# PCB_CAPA1.net
KiCad netlist of a schematic drawn in EAGLE
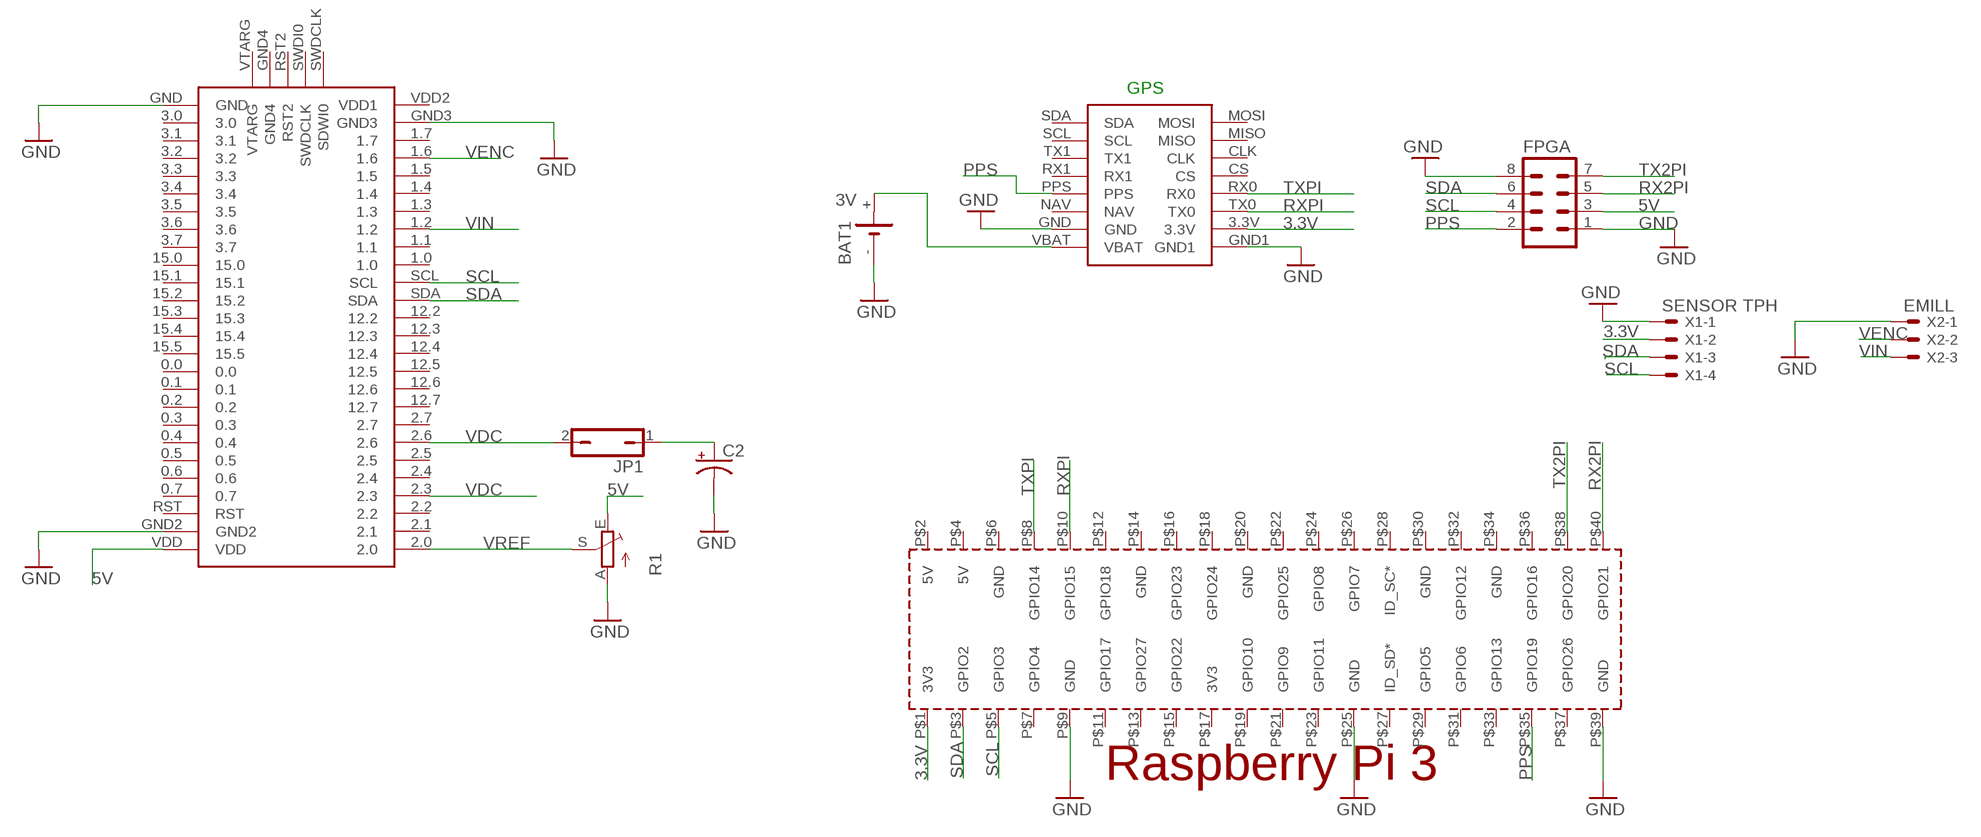
[diagram p0: schematic, sheet 1]

(export (version "E")
  (design (tool "Eeschema 10.0.6"))
  (components
    (comp (ref "BAT1")
      (value "3V")
      (footprint "eagle-import:CH291-1220LF")
      (libsource (lib "eagle-import") (part "CH291-1220LF"))
    )
    (comp (ref "C2")
      (value "CPOL-US153CLV-0807")
      (footprint "eagle-import:153CLV-0807")
      (libsource (lib "eagle-import") (part "CPOL-US153CLV-0807"))
    )
    (comp (ref "FPGA")
      (value "MA04-2")
      (footprint "eagle-import:MA04-2")
      (libsource (lib "eagle-import") (part "MA04-2"))
    )
    (comp (ref "GPS")
      (value "GPS_VENUS")
      (footprint "eagle-import:GPS_VENUS")
      (libsource (lib "eagle-import") (part "GPS_VENUS"))
    )
    (comp (ref "JP1")
      (value "JP1Q")
      (footprint "eagle-import:JP1")
      (libsource (lib "eagle-import") (part "JP1Q"))
    )
    (comp (ref "PCB1")
      (value "RPI3RPI3")
      (footprint "eagle-import:RPI3")
      (libsource (lib "eagle-import") (part "RPI3RPI3"))
    )
    (comp (ref "R1")
      (value "TRIM_EU-B90P")
      (footprint "eagle-import:SP19L")
      (libsource (lib "eagle-import") (part "TRIM_EU-B90P"))
    )
    (comp (ref "U$1")
      (value "PSOC_5LP")
      (footprint "eagle-import:PSOC_5LP")
      (libsource (lib "eagle-import") (part "PSOC_5LP"))
    )
    (comp (ref "X1")
      (value "SENSOR TPH")
      (footprint "eagle-import:22-23-2041")
      (fields (field (name "MF") "MOLEX") (field (name "MPN") "22-23-2041"))
      (libsource (lib "eagle-import") (part "22-23-2041"))
    )
    (comp (ref "X2")
      (value "EMILL")
      (footprint "eagle-import:22-23-2031")
      (fields (field (name "MF") "MOLEX") (field (name "MPN") "22-23-2031"))
      (libsource (lib "eagle-import") (part "22-23-2031"))
    )
  )
  (nets
    (net (code "1") (name "/3.3V") (class "Default")
      (node (ref "GPS") (pin "3.3V") (pinfunction "3.3V_3.3V") (pintype "bidirectional"))
      (node (ref "PCB1") (pin "P$1") (pinfunction "3V3_P$1") (pintype "bidirectional"))
      (node (ref "X1") (pin "2") (pinfunction "S_2") (pintype "passive"))
    )
    (net (code "2") (name "/5V") (class "Default")
      (node (ref "FPGA") (pin "3") (pinfunction "3_3") (pintype "passive"))
      (node (ref "R1") (pin "E") (pinfunction "E_E") (pintype "passive"))
      (node (ref "U$1") (pin "VDD") (pinfunction "VDD_VDD") (pintype "bidirectional"))
    )
    (net (code "3") (name "/PPS") (class "Default")
      (node (ref "FPGA") (pin "2") (pinfunction "2_2") (pintype "passive"))
      (node (ref "GPS") (pin "PPS") (pinfunction "PPS_PPS") (pintype "bidirectional"))
      (node (ref "PCB1") (pin "P$35") (pinfunction "GPIO19_P$35") (pintype "bidirectional"))
    )
    (net (code "4") (name "/RX2PI") (class "Default")
      (node (ref "FPGA") (pin "5") (pinfunction "5_5") (pintype "passive"))
      (node (ref "PCB1") (pin "P$40") (pinfunction "GPIO21_P$40") (pintype "bidirectional"))
    )
    (net (code "5") (name "/RXPI") (class "Default")
      (node (ref "GPS") (pin "TX0") (pinfunction "TX0_TX0") (pintype "bidirectional"))
      (node (ref "PCB1") (pin "P$10") (pinfunction "GPIO15_P$10") (pintype "bidirectional"))
    )
    (net (code "6") (name "/SCL") (class "Default")
      (node (ref "FPGA") (pin "4") (pinfunction "4_4") (pintype "passive"))
      (node (ref "PCB1") (pin "P$5") (pinfunction "GPIO3_P$5") (pintype "bidirectional"))
      (node (ref "U$1") (pin "SCL") (pinfunction "SCL_SCL") (pintype "bidirectional"))
      (node (ref "X1") (pin "4") (pinfunction "S_4") (pintype "passive"))
    )
    (net (code "7") (name "/SDA") (class "Default")
      (node (ref "FPGA") (pin "6") (pinfunction "6_6") (pintype "passive"))
      (node (ref "PCB1") (pin "P$3") (pinfunction "GPIO2_P$3") (pintype "bidirectional"))
      (node (ref "U$1") (pin "SDA") (pinfunction "SDA_SDA") (pintype "bidirectional"))
      (node (ref "X1") (pin "3") (pinfunction "S_3") (pintype "passive"))
    )
    (net (code "8") (name "/TX2PI") (class "Default")
      (node (ref "FPGA") (pin "7") (pinfunction "7_7") (pintype "passive"))
      (node (ref "PCB1") (pin "P$38") (pinfunction "GPIO20_P$38") (pintype "bidirectional"))
    )
    (net (code "9") (name "/TXPI") (class "Default")
      (node (ref "GPS") (pin "RX0") (pinfunction "RX0_RX0") (pintype "bidirectional"))
      (node (ref "PCB1") (pin "P$8") (pinfunction "GPIO14_P$8") (pintype "bidirectional"))
    )
    (net (code "10") (name "/VDC") (class "Default")
      (node (ref "JP1") (pin "2") (pinfunction "2_2") (pintype "passive"))
      (node (ref "U$1") (pin "2.3") (pinfunction "2.3_2.3") (pintype "bidirectional"))
      (node (ref "U$1") (pin "2.6") (pinfunction "2.6_2.6") (pintype "bidirectional"))
    )
    (net (code "11") (name "/VENC") (class "Default")
      (node (ref "U$1") (pin "1.6") (pinfunction "1.6_1.6") (pintype "bidirectional"))
      (node (ref "X2") (pin "2") (pinfunction "S_2") (pintype "passive"))
    )
    (net (code "12") (name "/VIN") (class "Default")
      (node (ref "U$1") (pin "1.2") (pinfunction "1.2_1.2") (pintype "bidirectional"))
      (node (ref "X2") (pin "3") (pinfunction "S_3") (pintype "passive"))
    )
    (net (code "13") (name "/VREF") (class "Default")
      (node (ref "R1") (pin "S") (pinfunction "S_S") (pintype "passive"))
      (node (ref "U$1") (pin "2.0") (pinfunction "2.0_2.0") (pintype "bidirectional"))
    )
    (net (code "14") (name "GND") (class "Default")
      (node (ref "BAT1") (pin "-") (pinfunction "-_-") (pintype "passive"))
      (node (ref "C2") (pin "-") (pinfunction "-_-") (pintype "passive"))
      (node (ref "FPGA") (pin "1") (pinfunction "1_1") (pintype "passive"))
      (node (ref "FPGA") (pin "8") (pinfunction "8_8") (pintype "passive"))
      (node (ref "GPS") (pin "GND") (pinfunction "GND_GND") (pintype "bidirectional"))
      (node (ref "GPS") (pin "GND1") (pinfunction "GND1_GND1") (pintype "bidirectional"))
      (node (ref "PCB1") (pin "P$25") (pinfunction "GND_P$25") (pintype "bidirectional"))
      (node (ref "PCB1") (pin "P$39") (pinfunction "GND_P$39") (pintype "bidirectional"))
      (node (ref "PCB1") (pin "P$9") (pinfunction "GND_P$9") (pintype "bidirectional"))
      (node (ref "R1") (pin "A") (pinfunction "A_A") (pintype "passive"))
      (node (ref "U$1") (pin "GND") (pinfunction "GND_GND") (pintype "bidirectional"))
      (node (ref "U$1") (pin "GND2") (pinfunction "GND2_GND2") (pintype "bidirectional"))
      (node (ref "U$1") (pin "GND3") (pinfunction "GND3_GND3") (pintype "bidirectional"))
      (node (ref "X1") (pin "1") (pinfunction "S_1") (pintype "passive"))
      (node (ref "X2") (pin "1") (pinfunction "S_1") (pintype "passive"))
    )
    (net (code "15") (name "Net-(BAT1-Pad+)") (class "Default")
      (node (ref "BAT1") (pin "+") (pinfunction "+_+") (pintype "passive"))
      (node (ref "GPS") (pin "VBAT") (pinfunction "VBAT_VBAT") (pintype "bidirectional"))
    )
    (net (code "16") (name "Net-(C2-Pad+)") (class "Default")
      (node (ref "C2") (pin "+") (pinfunction "+_+") (pintype "passive"))
      (node (ref "JP1") (pin "1") (pinfunction "1_1") (pintype "passive"))
    )
    (net (code "17") (name "unconnected-(GPS-PadCLK)") (class "Default")
      (node (ref "GPS") (pin "CLK") (pinfunction "CLK_CLK") (pintype "bidirectional"))
    )
    (net (code "18") (name "unconnected-(GPS-PadCS)") (class "Default")
      (node (ref "GPS") (pin "CS") (pinfunction "CS_CS") (pintype "bidirectional"))
    )
    (net (code "19") (name "unconnected-(GPS-PadMISO)") (class "Default")
      (node (ref "GPS") (pin "MISO") (pinfunction "MISO_MISO") (pintype "bidirectional"))
    )
    (net (code "20") (name "unconnected-(GPS-PadMOSI)") (class "Default")
      (node (ref "GPS") (pin "MOSI") (pinfunction "MOSI_MOSI") (pintype "bidirectional"))
    )
    (net (code "21") (name "unconnected-(GPS-PadNAV)") (class "Default")
      (node (ref "GPS") (pin "NAV") (pinfunction "NAV_NAV") (pintype "bidirectional"))
    )
    (net (code "22") (name "unconnected-(GPS-PadRX1)") (class "Default")
      (node (ref "GPS") (pin "RX1") (pinfunction "RX1_RX1") (pintype "bidirectional"))
    )
    (net (code "23") (name "unconnected-(GPS-PadSCL)") (class "Default")
      (node (ref "GPS") (pin "SCL") (pinfunction "SCL_SCL") (pintype "bidirectional"))
    )
    (net (code "24") (name "unconnected-(GPS-PadSDA)") (class "Default")
      (node (ref "GPS") (pin "SDA") (pinfunction "SDA_SDA") (pintype "bidirectional"))
    )
    (net (code "25") (name "unconnected-(GPS-PadTX1)") (class "Default")
      (node (ref "GPS") (pin "TX1") (pinfunction "TX1_TX1") (pintype "bidirectional"))
    )
    (net (code "26") (name "unconnected-(PCB1-3V3-PadP$17)") (class "Default")
      (node (ref "PCB1") (pin "P$17") (pinfunction "3V3_P$17") (pintype "bidirectional"))
    )
    (net (code "27") (name "unconnected-(PCB1-5V-PadP$2)") (class "Default")
      (node (ref "PCB1") (pin "P$2") (pinfunction "5V_P$2") (pintype "bidirectional"))
    )
    (net (code "28") (name "unconnected-(PCB1-5V-PadP$4)") (class "Default")
      (node (ref "PCB1") (pin "P$4") (pinfunction "5V_P$4") (pintype "bidirectional"))
    )
    (net (code "29") (name "unconnected-(PCB1-GND-PadP$6)") (class "Default")
      (node (ref "PCB1") (pin "P$6") (pinfunction "GND_P$6") (pintype "bidirectional"))
    )
    (net (code "30") (name "unconnected-(PCB1-GND-PadP$14)") (class "Default")
      (node (ref "PCB1") (pin "P$14") (pinfunction "GND_P$14") (pintype "bidirectional"))
    )
    (net (code "31") (name "unconnected-(PCB1-GND-PadP$20)") (class "Default")
      (node (ref "PCB1") (pin "P$20") (pinfunction "GND_P$20") (pintype "bidirectional"))
    )
    (net (code "32") (name "unconnected-(PCB1-GND-PadP$30)") (class "Default")
      (node (ref "PCB1") (pin "P$30") (pinfunction "GND_P$30") (pintype "bidirectional"))
    )
    (net (code "33") (name "unconnected-(PCB1-GND-PadP$34)") (class "Default")
      (node (ref "PCB1") (pin "P$34") (pinfunction "GND_P$34") (pintype "bidirectional"))
    )
    (net (code "34") (name "unconnected-(PCB1-GPIO4-PadP$7)") (class "Default")
      (node (ref "PCB1") (pin "P$7") (pinfunction "GPIO4_P$7") (pintype "bidirectional"))
    )
    (net (code "35") (name "unconnected-(PCB1-GPIO5-PadP$29)") (class "Default")
      (node (ref "PCB1") (pin "P$29") (pinfunction "GPIO5_P$29") (pintype "bidirectional"))
    )
    (net (code "36") (name "unconnected-(PCB1-GPIO6-PadP$31)") (class "Default")
      (node (ref "PCB1") (pin "P$31") (pinfunction "GPIO6_P$31") (pintype "bidirectional"))
    )
    (net (code "37") (name "unconnected-(PCB1-GPIO7-PadP$26)") (class "Default")
      (node (ref "PCB1") (pin "P$26") (pinfunction "GPIO7_P$26") (pintype "bidirectional"))
    )
    (net (code "38") (name "unconnected-(PCB1-GPIO8-PadP$24)") (class "Default")
      (node (ref "PCB1") (pin "P$24") (pinfunction "GPIO8_P$24") (pintype "bidirectional"))
    )
    (net (code "39") (name "unconnected-(PCB1-GPIO9-PadP$21)") (class "Default")
      (node (ref "PCB1") (pin "P$21") (pinfunction "GPIO9_P$21") (pintype "bidirectional"))
    )
    (net (code "40") (name "unconnected-(PCB1-GPIO10-PadP$19)") (class "Default")
      (node (ref "PCB1") (pin "P$19") (pinfunction "GPIO10_P$19") (pintype "bidirectional"))
    )
    (net (code "41") (name "unconnected-(PCB1-GPIO11-PadP$23)") (class "Default")
      (node (ref "PCB1") (pin "P$23") (pinfunction "GPIO11_P$23") (pintype "bidirectional"))
    )
    (net (code "42") (name "unconnected-(PCB1-GPIO12-PadP$32)") (class "Default")
      (node (ref "PCB1") (pin "P$32") (pinfunction "GPIO12_P$32") (pintype "bidirectional"))
    )
    (net (code "43") (name "unconnected-(PCB1-GPIO13-PadP$33)") (class "Default")
      (node (ref "PCB1") (pin "P$33") (pinfunction "GPIO13_P$33") (pintype "bidirectional"))
    )
    (net (code "44") (name "unconnected-(PCB1-GPIO16-PadP$36)") (class "Default")
      (node (ref "PCB1") (pin "P$36") (pinfunction "GPIO16_P$36") (pintype "bidirectional"))
    )
    (net (code "45") (name "unconnected-(PCB1-GPIO17-PadP$11)") (class "Default")
      (node (ref "PCB1") (pin "P$11") (pinfunction "GPIO17_P$11") (pintype "bidirectional"))
    )
    (net (code "46") (name "unconnected-(PCB1-GPIO18-PadP$12)") (class "Default")
      (node (ref "PCB1") (pin "P$12") (pinfunction "GPIO18_P$12") (pintype "bidirectional"))
    )
    (net (code "47") (name "unconnected-(PCB1-GPIO22-PadP$15)") (class "Default")
      (node (ref "PCB1") (pin "P$15") (pinfunction "GPIO22_P$15") (pintype "bidirectional"))
    )
    (net (code "48") (name "unconnected-(PCB1-GPIO23-PadP$16)") (class "Default")
      (node (ref "PCB1") (pin "P$16") (pinfunction "GPIO23_P$16") (pintype "bidirectional"))
    )
    (net (code "49") (name "unconnected-(PCB1-GPIO24-PadP$18)") (class "Default")
      (node (ref "PCB1") (pin "P$18") (pinfunction "GPIO24_P$18") (pintype "bidirectional"))
    )
    (net (code "50") (name "unconnected-(PCB1-GPIO25-PadP$22)") (class "Default")
      (node (ref "PCB1") (pin "P$22") (pinfunction "GPIO25_P$22") (pintype "bidirectional"))
    )
    (net (code "51") (name "unconnected-(PCB1-GPIO26-PadP$37)") (class "Default")
      (node (ref "PCB1") (pin "P$37") (pinfunction "GPIO26_P$37") (pintype "bidirectional"))
    )
    (net (code "52") (name "unconnected-(PCB1-GPIO27-PadP$13)") (class "Default")
      (node (ref "PCB1") (pin "P$13") (pinfunction "GPIO27_P$13") (pintype "bidirectional"))
    )
    (net (code "53") (name "unconnected-(PCB1-ID_SC*-PadP$28)") (class "Default")
      (node (ref "PCB1") (pin "P$28") (pinfunction "ID_SC*_P$28") (pintype "bidirectional"))
    )
    (net (code "54") (name "unconnected-(PCB1-ID_SD*-PadP$27)") (class "Default")
      (node (ref "PCB1") (pin "P$27") (pinfunction "ID_SD*_P$27") (pintype "bidirectional"))
    )
    (net (code "55") (name "unconnected-(U$1-Pad0.0)") (class "Default")
      (node (ref "U$1") (pin "0.0") (pinfunction "0.0_0.0") (pintype "bidirectional"))
    )
    (net (code "56") (name "unconnected-(U$1-Pad0.1)") (class "Default")
      (node (ref "U$1") (pin "0.1") (pinfunction "0.1_0.1") (pintype "bidirectional"))
    )
    (net (code "57") (name "unconnected-(U$1-Pad0.2)") (class "Default")
      (node (ref "U$1") (pin "0.2") (pinfunction "0.2_0.2") (pintype "bidirectional"))
    )
    (net (code "58") (name "unconnected-(U$1-Pad0.3)") (class "Default")
      (node (ref "U$1") (pin "0.3") (pinfunction "0.3_0.3") (pintype "bidirectional"))
    )
    (net (code "59") (name "unconnected-(U$1-Pad0.4)") (class "Default")
      (node (ref "U$1") (pin "0.4") (pinfunction "0.4_0.4") (pintype "bidirectional"))
    )
    (net (code "60") (name "unconnected-(U$1-Pad0.5)") (class "Default")
      (node (ref "U$1") (pin "0.5") (pinfunction "0.5_0.5") (pintype "bidirectional"))
    )
    (net (code "61") (name "unconnected-(U$1-Pad0.6)") (class "Default")
      (node (ref "U$1") (pin "0.6") (pinfunction "0.6_0.6") (pintype "bidirectional"))
    )
    (net (code "62") (name "unconnected-(U$1-Pad0.7)") (class "Default")
      (node (ref "U$1") (pin "0.7") (pinfunction "0.7_0.7") (pintype "bidirectional"))
    )
    (net (code "63") (name "unconnected-(U$1-Pad1.0)") (class "Default")
      (node (ref "U$1") (pin "1.0") (pinfunction "1.0_1.0") (pintype "bidirectional"))
    )
    (net (code "64") (name "unconnected-(U$1-Pad1.1)") (class "Default")
      (node (ref "U$1") (pin "1.1") (pinfunction "1.1_1.1") (pintype "bidirectional"))
    )
    (net (code "65") (name "unconnected-(U$1-Pad1.3)") (class "Default")
      (node (ref "U$1") (pin "1.3") (pinfunction "1.3_1.3") (pintype "bidirectional"))
    )
    (net (code "66") (name "unconnected-(U$1-Pad1.4)") (class "Default")
      (node (ref "U$1") (pin "1.4") (pinfunction "1.4_1.4") (pintype "bidirectional"))
    )
    (net (code "67") (name "unconnected-(U$1-Pad1.5)") (class "Default")
      (node (ref "U$1") (pin "1.5") (pinfunction "1.5_1.5") (pintype "bidirectional"))
    )
    (net (code "68") (name "unconnected-(U$1-Pad1.7)") (class "Default")
      (node (ref "U$1") (pin "1.7") (pinfunction "1.7_1.7") (pintype "bidirectional"))
    )
    (net (code "69") (name "unconnected-(U$1-Pad2.1)") (class "Default")
      (node (ref "U$1") (pin "2.1") (pinfunction "2.1_2.1") (pintype "bidirectional"))
    )
    (net (code "70") (name "unconnected-(U$1-Pad2.2)") (class "Default")
      (node (ref "U$1") (pin "2.2") (pinfunction "2.2_2.2") (pintype "bidirectional"))
    )
    (net (code "71") (name "unconnected-(U$1-Pad2.4)") (class "Default")
      (node (ref "U$1") (pin "2.4") (pinfunction "2.4_2.4") (pintype "bidirectional"))
    )
    (net (code "72") (name "unconnected-(U$1-Pad2.5)") (class "Default")
      (node (ref "U$1") (pin "2.5") (pinfunction "2.5_2.5") (pintype "bidirectional"))
    )
    (net (code "73") (name "unconnected-(U$1-Pad2.7)") (class "Default")
      (node (ref "U$1") (pin "2.7") (pinfunction "2.7_2.7") (pintype "bidirectional"))
    )
    (net (code "74") (name "unconnected-(U$1-Pad3.0)") (class "Default")
      (node (ref "U$1") (pin "3.0") (pinfunction "3.0_3.0") (pintype "bidirectional"))
    )
    (net (code "75") (name "unconnected-(U$1-Pad3.1)") (class "Default")
      (node (ref "U$1") (pin "3.1") (pinfunction "3.1_3.1") (pintype "bidirectional"))
    )
    (net (code "76") (name "unconnected-(U$1-Pad3.2)") (class "Default")
      (node (ref "U$1") (pin "3.2") (pinfunction "3.2_3.2") (pintype "bidirectional"))
    )
    (net (code "77") (name "unconnected-(U$1-Pad3.3)") (class "Default")
      (node (ref "U$1") (pin "3.3") (pinfunction "3.3_3.3") (pintype "bidirectional"))
    )
    (net (code "78") (name "unconnected-(U$1-Pad3.4)") (class "Default")
      (node (ref "U$1") (pin "3.4") (pinfunction "3.4_3.4") (pintype "bidirectional"))
    )
    (net (code "79") (name "unconnected-(U$1-Pad3.5)") (class "Default")
      (node (ref "U$1") (pin "3.5") (pinfunction "3.5_3.5") (pintype "bidirectional"))
    )
    (net (code "80") (name "unconnected-(U$1-Pad3.6)") (class "Default")
      (node (ref "U$1") (pin "3.6") (pinfunction "3.6_3.6") (pintype "bidirectional"))
    )
    (net (code "81") (name "unconnected-(U$1-Pad3.7)") (class "Default")
      (node (ref "U$1") (pin "3.7") (pinfunction "3.7_3.7") (pintype "bidirectional"))
    )
    (net (code "82") (name "unconnected-(U$1-Pad12.2)") (class "Default")
      (node (ref "U$1") (pin "12.2") (pinfunction "12.2_12.2") (pintype "bidirectional"))
    )
    (net (code "83") (name "unconnected-(U$1-Pad12.3)") (class "Default")
      (node (ref "U$1") (pin "12.3") (pinfunction "12.3_12.3") (pintype "bidirectional"))
    )
    (net (code "84") (name "unconnected-(U$1-Pad12.4)") (class "Default")
      (node (ref "U$1") (pin "12.4") (pinfunction "12.4_12.4") (pintype "bidirectional"))
    )
    (net (code "85") (name "unconnected-(U$1-Pad12.5)") (class "Default")
      (node (ref "U$1") (pin "12.5") (pinfunction "12.5_12.5") (pintype "bidirectional"))
    )
    (net (code "86") (name "unconnected-(U$1-Pad12.6)") (class "Default")
      (node (ref "U$1") (pin "12.6") (pinfunction "12.6_12.6") (pintype "bidirectional"))
    )
    (net (code "87") (name "unconnected-(U$1-Pad12.7)") (class "Default")
      (node (ref "U$1") (pin "12.7") (pinfunction "12.7_12.7") (pintype "bidirectional"))
    )
    (net (code "88") (name "unconnected-(U$1-Pad15.0)") (class "Default")
      (node (ref "U$1") (pin "15.0") (pinfunction "15.0_15.0") (pintype "bidirectional"))
    )
    (net (code "89") (name "unconnected-(U$1-Pad15.1)") (class "Default")
      (node (ref "U$1") (pin "15.1") (pinfunction "15.1_15.1") (pintype "bidirectional"))
    )
    (net (code "90") (name "unconnected-(U$1-Pad15.2)") (class "Default")
      (node (ref "U$1") (pin "15.2") (pinfunction "15.2_15.2") (pintype "bidirectional"))
    )
    (net (code "91") (name "unconnected-(U$1-Pad15.3)") (class "Default")
      (node (ref "U$1") (pin "15.3") (pinfunction "15.3_15.3") (pintype "bidirectional"))
    )
    (net (code "92") (name "unconnected-(U$1-Pad15.4)") (class "Default")
      (node (ref "U$1") (pin "15.4") (pinfunction "15.4_15.4") (pintype "bidirectional"))
    )
    (net (code "93") (name "unconnected-(U$1-Pad15.5)") (class "Default")
      (node (ref "U$1") (pin "15.5") (pinfunction "15.5_15.5") (pintype "bidirectional"))
    )
    (net (code "94") (name "unconnected-(U$1-PadGND4)") (class "Default")
      (node (ref "U$1") (pin "GND4") (pinfunction "GND4_GND4") (pintype "bidirectional"))
    )
    (net (code "95") (name "unconnected-(U$1-PadRST)") (class "Default")
      (node (ref "U$1") (pin "RST") (pinfunction "RST_RST") (pintype "bidirectional"))
    )
    (net (code "96") (name "unconnected-(U$1-PadRST2)") (class "Default")
      (node (ref "U$1") (pin "RST2") (pinfunction "RST2_RST2") (pintype "bidirectional"))
    )
    (net (code "97") (name "unconnected-(U$1-PadVTARG)") (class "Default")
      (node (ref "U$1") (pin "VTARG") (pinfunction "VTARG_VTARG") (pintype "bidirectional"))
    )
    (net (code "98") (name "unconnected-(U$1-SDWI0-PadSWDCLK)") (class "Default")
      (node (ref "U$1") (pin "SWDCLK") (pinfunction "SDWI0_SWDCLK") (pintype "bidirectional"))
    )
    (net (code "99") (name "unconnected-(U$1-SWDCLK-PadSWDI0)") (class "Default")
      (node (ref "U$1") (pin "SWDI0") (pinfunction "SWDCLK_SWDI0") (pintype "bidirectional"))
    )
    (net (code "100") (name "unconnected-(U$1-VDD1-PadVDD2)") (class "Default")
      (node (ref "U$1") (pin "VDD2") (pinfunction "VDD1_VDD2") (pintype "bidirectional"))
    )
  )
)
